# nrf5340_qkaa_Config3.net
KiCad netlist of a schematic drawn in EAGLE
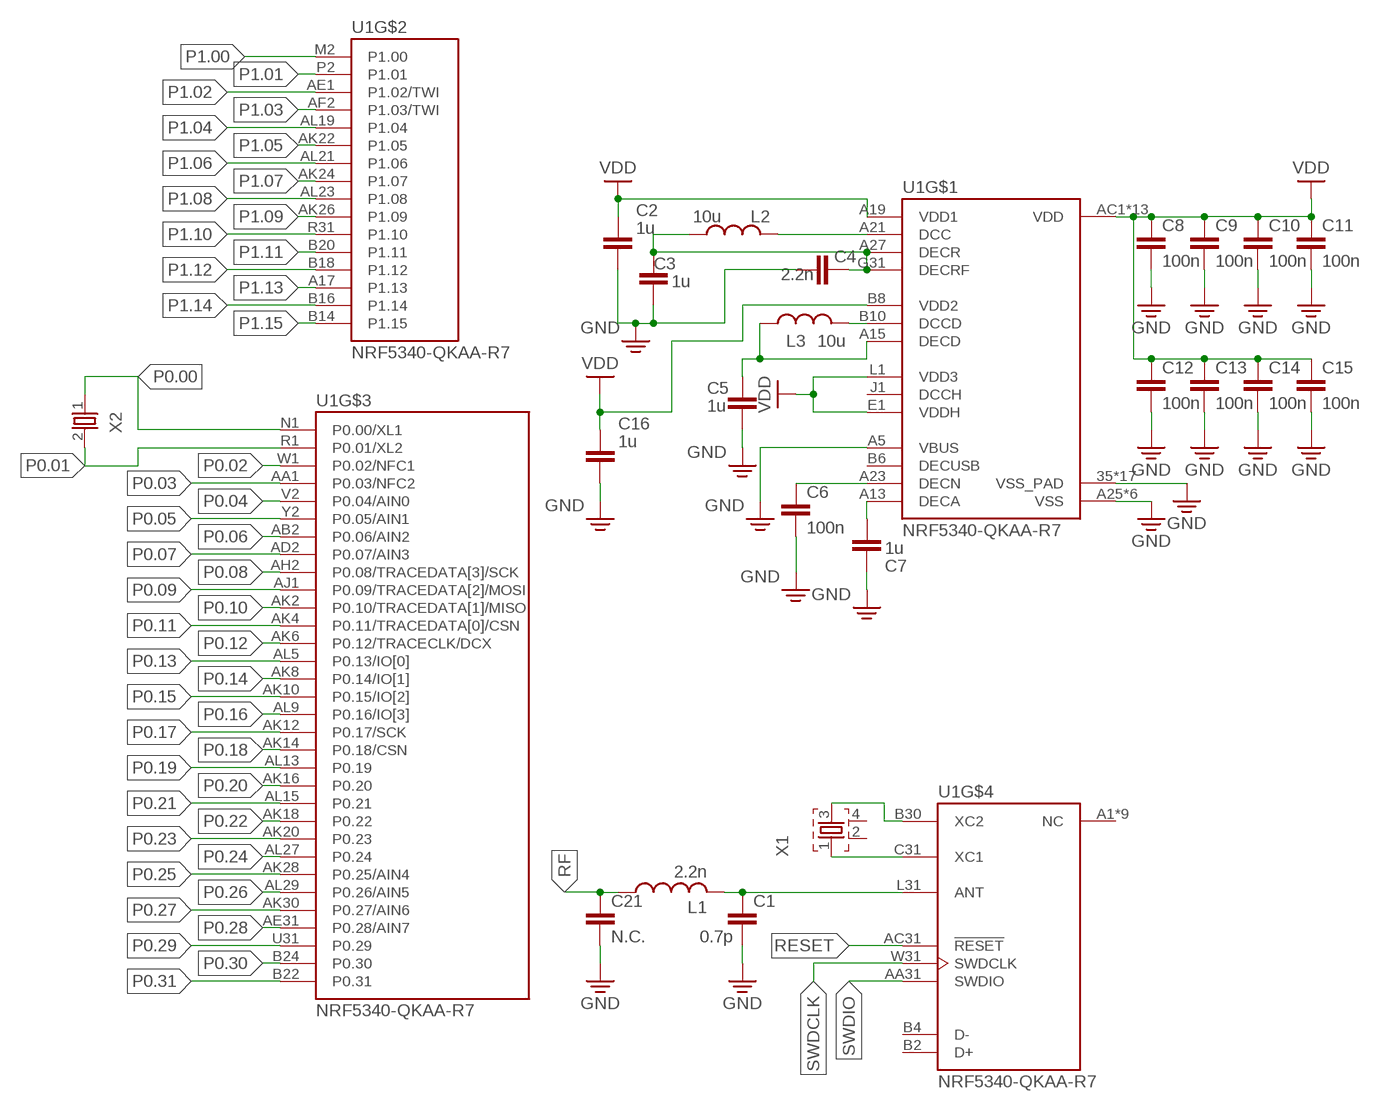
[diagram p0: schematic, sheet 1]

(export (version "E")
  (design (tool "Eeschema 10.0.6"))
  (components
    (comp (ref "C1")
      (value "0.7p")
      (footprint "eagle-import:RESC0201_N")
      (libsource (lib "eagle-import") (part "CAPACITOR_0201_N"))
    )
    (comp (ref "C2")
      (value "1u")
      (footprint "eagle-import:CAPC1005X60")
      (libsource (lib "eagle-import") (part "CCHIP-0402(1005-METRIC)_"))
    )
    (comp (ref "C3")
      (value "1u")
      (footprint "eagle-import:CAPC1005X60")
      (libsource (lib "eagle-import") (part "CCHIP-0402(1005-METRIC)_"))
    )
    (comp (ref "C4")
      (value "2.2n")
      (footprint "eagle-import:RESC0201_N")
      (libsource (lib "eagle-import") (part "CAPACITOR_0201_N"))
    )
    (comp (ref "C5")
      (value "1u")
      (footprint "eagle-import:CAPC1005X60")
      (libsource (lib "eagle-import") (part "CCHIP-0402(1005-METRIC)_"))
    )
    (comp (ref "C6")
      (value "100n")
      (footprint "eagle-import:RESC0201_N")
      (libsource (lib "eagle-import") (part "CAPACITOR_0201_N"))
    )
    (comp (ref "C7")
      (value "1u")
      (footprint "eagle-import:CAPC1005X60")
      (libsource (lib "eagle-import") (part "CCHIP-0402(1005-METRIC)_"))
    )
    (comp (ref "C8")
      (value "100n")
      (footprint "eagle-import:RESC0201_N")
      (libsource (lib "eagle-import") (part "CAPACITOR_0201_N"))
    )
    (comp (ref "C9")
      (value "100n")
      (footprint "eagle-import:RESC0201_N")
      (libsource (lib "eagle-import") (part "CAPACITOR_0201_N"))
    )
    (comp (ref "C10")
      (value "100n")
      (footprint "eagle-import:RESC0201_N")
      (libsource (lib "eagle-import") (part "CAPACITOR_0201_N"))
    )
    (comp (ref "C11")
      (value "100n")
      (footprint "eagle-import:RESC0201_N")
      (libsource (lib "eagle-import") (part "CAPACITOR_0201_N"))
    )
    (comp (ref "C12")
      (value "100n")
      (footprint "eagle-import:RESC0201_N")
      (libsource (lib "eagle-import") (part "CAPACITOR_0201_N"))
    )
    (comp (ref "C13")
      (value "100n")
      (footprint "eagle-import:RESC0201_N")
      (libsource (lib "eagle-import") (part "CAPACITOR_0201_N"))
    )
    (comp (ref "C14")
      (value "100n")
      (footprint "eagle-import:RESC0201_N")
      (libsource (lib "eagle-import") (part "CAPACITOR_0201_N"))
    )
    (comp (ref "C15")
      (value "100n")
      (footprint "eagle-import:RESC0201_N")
      (libsource (lib "eagle-import") (part "CAPACITOR_0201_N"))
    )
    (comp (ref "C16")
      (value "1u")
      (footprint "eagle-import:CAPC1005X60")
      (libsource (lib "eagle-import") (part "CCHIP-0402(1005-METRIC)_"))
    )
    (comp (ref "C21")
      (value "N.C.")
      (footprint "eagle-import:RESC0201_N")
      (libsource (lib "eagle-import") (part "CAPACITOR_0201_N"))
    )
    (comp (ref "L1")
      (value "2.2n")
      (footprint "eagle-import:RESC0201_N")
      (libsource (lib "eagle-import") (part "INDUCTOR_0201_N"))
    )
    (comp (ref "L2")
      (value "10u")
      (footprint "eagle-import:INDC1608X95N")
      (libsource (lib "eagle-import") (part "LCHIP-0603(1608-METRIC)_"))
    )
    (comp (ref "L3")
      (value "10u")
      (footprint "eagle-import:INDC1608X95N")
      (libsource (lib "eagle-import") (part "LCHIP-0603(1608-METRIC)_"))
    )
    (comp (ref "U1")
      (value "NRF5340-QKAA-R7")
      (footprint "eagle-import:XCVR_NRF5340-QKAA-R7")
      (fields (field (name "MANUFACTURER") "Nordic Semiconductor"))
      (libsource (lib "eagle-import") (part "NRF5340-QKAA-R7"))
    )
    (comp (ref "X1")
      (value "XTAL_32MHZ")
      (footprint "eagle-import:BT-XTAL_2016_N")
      (libsource (lib "eagle-import") (part "XTAL_32MHZ"))
    )
    (comp (ref "X2")
      (value "XTAL_32KHZ")
      (footprint "eagle-import:XTAL_3215_N")
      (libsource (lib "eagle-import") (part "XTAL_32KHZ"))
    )
  )
  (nets
    (net (code "1") (name "/DCCH") (class "Default")
      (node (ref "U1") (pin "J1") (pinfunction "DCCH_J1") (pintype "power_in"))
    )
    (net (code "2") (name "/DECUSB") (class "Default")
      (node (ref "U1") (pin "B6") (pinfunction "DECUSB_B6") (pintype "power_in"))
    )
    (net (code "3") (name "GND") (class "Default")
      (node (ref "C1") (pin "2") (pinfunction "2_2") (pintype "passive"))
      (node (ref "C10") (pin "2") (pinfunction "2_2") (pintype "passive"))
      (node (ref "C11") (pin "2") (pinfunction "2_2") (pintype "passive"))
      (node (ref "C12") (pin "2") (pinfunction "2_2") (pintype "passive"))
      (node (ref "C13") (pin "2") (pinfunction "2_2") (pintype "passive"))
      (node (ref "C14") (pin "2") (pinfunction "2_2") (pintype "passive"))
      (node (ref "C15") (pin "2") (pinfunction "2_2") (pintype "passive"))
      (node (ref "C16") (pin "2") (pinfunction "2_2") (pintype "passive"))
      (node (ref "C2") (pin "2") (pinfunction "2_2") (pintype "passive"))
      (node (ref "C21") (pin "2") (pinfunction "2_2") (pintype "passive"))
      (node (ref "C3") (pin "2") (pinfunction "2_2") (pintype "passive"))
      (node (ref "C4") (pin "2") (pinfunction "2_2") (pintype "passive"))
      (node (ref "C5") (pin "2") (pinfunction "2_2") (pintype "passive"))
      (node (ref "C6") (pin "2") (pinfunction "2_2") (pintype "passive"))
      (node (ref "C7") (pin "2") (pinfunction "2_2") (pintype "passive"))
      (node (ref "C8") (pin "2") (pinfunction "2_2") (pintype "passive"))
      (node (ref "C9") (pin "2") (pinfunction "2_2") (pintype "passive"))
      (node (ref "U1") (pin "104") (pinfunction "VSS_PAD_104") (pintype "power_in"))
      (node (ref "U1") (pin "35") (pinfunction "VSS_PAD_35") (pintype "power_in"))
      (node (ref "U1") (pin "36") (pinfunction "VSS_PAD_36") (pintype "power_in"))
      (node (ref "U1") (pin "37") (pinfunction "VSS_PAD_37") (pintype "power_in"))
      (node (ref "U1") (pin "38") (pinfunction "VSS_PAD_38") (pintype "power_in"))
      (node (ref "U1") (pin "39") (pinfunction "VSS_PAD_39") (pintype "power_in"))
      (node (ref "U1") (pin "40") (pinfunction "VSS_PAD_40") (pintype "power_in"))
      (node (ref "U1") (pin "41") (pinfunction "VSS_PAD_41") (pintype "power_in"))
      (node (ref "U1") (pin "43") (pinfunction "VSS_PAD_43") (pintype "power_in"))
      (node (ref "U1") (pin "44") (pinfunction "VSS_PAD_44") (pintype "power_in"))
      (node (ref "U1") (pin "45") (pinfunction "VSS_PAD_45") (pintype "power_in"))
      (node (ref "U1") (pin "46") (pinfunction "VSS_PAD_46") (pintype "power_in"))
      (node (ref "U1") (pin "47") (pinfunction "VSS_PAD_47") (pintype "power_in"))
      (node (ref "U1") (pin "48") (pinfunction "VSS_PAD_48") (pintype "power_in"))
      (node (ref "U1") (pin "49") (pinfunction "VSS_PAD_49") (pintype "power_in"))
      (node (ref "U1") (pin "50") (pinfunction "VSS_PAD_50") (pintype "power_in"))
      (node (ref "U1") (pin "51") (pinfunction "VSS_PAD_51") (pintype "power_in"))
      (node (ref "U1") (pin "A25") (pinfunction "VSS_A25") (pintype "power_in"))
      (node (ref "U1") (pin "A5") (pinfunction "VBUS_A5") (pintype "power_in"))
      (node (ref "U1") (pin "B12") (pinfunction "VSS_B12") (pintype "power_in"))
      (node (ref "U1") (pin "B26") (pinfunction "VSS_B26") (pintype "power_in"))
      (node (ref "U1") (pin "G1") (pinfunction "VSS_G1") (pintype "power_in"))
      (node (ref "U1") (pin "H2") (pinfunction "VSS_H2") (pintype "power_in"))
      (node (ref "U1") (pin "J31") (pinfunction "VSS_J31") (pintype "power_in"))
    )
    (net (code "4") (name "Net-(U1A-DCC)") (class "Default")
      (node (ref "L2") (pin "2") (pinfunction "2_2") (pintype "passive"))
      (node (ref "U1") (pin "A21") (pinfunction "DCC_A21") (pintype "power_in"))
    )
    (net (code "5") (name "Net-(U1A-DCCD)") (class "Default")
      (node (ref "L3") (pin "2") (pinfunction "2_2") (pintype "passive"))
      (node (ref "U1") (pin "B10") (pinfunction "DCCD_B10") (pintype "power_in"))
    )
    (net (code "6") (name "Net-(U1A-DECA)") (class "Default")
      (node (ref "C7") (pin "1") (pinfunction "1_1") (pintype "passive"))
      (node (ref "U1") (pin "A13") (pinfunction "DECA_A13") (pintype "power_in"))
    )
    (net (code "7") (name "Net-(U1A-DECD)") (class "Default")
      (node (ref "C5") (pin "1") (pinfunction "1_1") (pintype "passive"))
      (node (ref "L3") (pin "1") (pinfunction "1_1") (pintype "passive"))
      (node (ref "U1") (pin "A15") (pinfunction "DECD_A15") (pintype "power_in"))
    )
    (net (code "8") (name "Net-(U1A-DECN)") (class "Default")
      (node (ref "C6") (pin "1") (pinfunction "1_1") (pintype "passive"))
      (node (ref "U1") (pin "A23") (pinfunction "DECN_A23") (pintype "power_in"))
    )
    (net (code "9") (name "Net-(U1A-DECR)") (class "Default")
      (node (ref "C3") (pin "1") (pinfunction "1_1") (pintype "passive"))
      (node (ref "C4") (pin "1") (pinfunction "1_1") (pintype "passive"))
      (node (ref "L2") (pin "1") (pinfunction "1_1") (pintype "passive"))
      (node (ref "U1") (pin "A27") (pinfunction "DECR_A27") (pintype "power_in"))
      (node (ref "U1") (pin "G31") (pinfunction "DECRF_G31") (pintype "power_in"))
    )
    (net (code "10") (name "Net-(U1D-ANT)") (class "Default")
      (node (ref "C1") (pin "1") (pinfunction "1_1") (pintype "passive"))
      (node (ref "L1") (pin "2") (pinfunction "2_2") (pintype "passive"))
      (node (ref "U1") (pin "L31") (pinfunction "ANT_L31") (pintype "bidirectional"))
    )
    (net (code "11") (name "Net-(U1D-XC1)") (class "Default")
      (node (ref "U1") (pin "C31") (pinfunction "XC1_C31") (pintype "input"))
      (node (ref "X1") (pin "1") (pinfunction "1_1") (pintype "passive"))
    )
    (net (code "12") (name "Net-(U1D-XC2)") (class "Default")
      (node (ref "U1") (pin "B30") (pinfunction "XC2_B30") (pintype "output"))
      (node (ref "X1") (pin "3") (pinfunction "3_3") (pintype "passive"))
    )
    (net (code "13") (name "P0.00") (class "Default")
      (node (ref "U1") (pin "N1") (pinfunction "P0.00/XL1_N1") (pintype "bidirectional"))
      (node (ref "X2") (pin "1") (pinfunction "1_1") (pintype "passive"))
    )
    (net (code "14") (name "P0.01") (class "Default")
      (node (ref "U1") (pin "R1") (pinfunction "P0.01/XL2_R1") (pintype "bidirectional"))
      (node (ref "X2") (pin "2") (pinfunction "2_2") (pintype "passive"))
    )
    (net (code "15") (name "P0.02") (class "Default")
      (node (ref "U1") (pin "W1") (pinfunction "P0.02/NFC1_W1") (pintype "bidirectional"))
    )
    (net (code "16") (name "P0.03") (class "Default")
      (node (ref "U1") (pin "AA1") (pinfunction "P0.03/NFC2_AA1") (pintype "bidirectional"))
    )
    (net (code "17") (name "P0.04") (class "Default")
      (node (ref "U1") (pin "V2") (pinfunction "P0.04/AIN0_V2") (pintype "bidirectional"))
    )
    (net (code "18") (name "P0.05") (class "Default")
      (node (ref "U1") (pin "Y2") (pinfunction "P0.05/AIN1_Y2") (pintype "bidirectional"))
    )
    (net (code "19") (name "P0.06") (class "Default")
      (node (ref "U1") (pin "AB2") (pinfunction "P0.06/AIN2_AB2") (pintype "bidirectional"))
    )
    (net (code "20") (name "P0.07") (class "Default")
      (node (ref "U1") (pin "AD2") (pinfunction "P0.07/AIN3_AD2") (pintype "bidirectional"))
    )
    (net (code "21") (name "P0.08") (class "Default")
      (node (ref "U1") (pin "AH2") (pinfunction "P0.08/TRACEDATA[3]/SCK_AH2") (pintype "bidirectional"))
    )
    (net (code "22") (name "P0.09") (class "Default")
      (node (ref "U1") (pin "AJ1") (pinfunction "P0.09/TRACEDATA[2]/MOSI_AJ1") (pintype "bidirectional"))
    )
    (net (code "23") (name "P0.10") (class "Default")
      (node (ref "U1") (pin "AK2") (pinfunction "P0.10/TRACEDATA[1]/MISO_AK2") (pintype "bidirectional"))
    )
    (net (code "24") (name "P0.11") (class "Default")
      (node (ref "U1") (pin "AK4") (pinfunction "P0.11/TRACEDATA[0]/CSN_AK4") (pintype "bidirectional"))
    )
    (net (code "25") (name "P0.12") (class "Default")
      (node (ref "U1") (pin "AK6") (pinfunction "P0.12/TRACECLK/DCX_AK6") (pintype "bidirectional"))
    )
    (net (code "26") (name "P0.13") (class "Default")
      (node (ref "U1") (pin "AL5") (pinfunction "P0.13/IO[0]_AL5") (pintype "bidirectional"))
    )
    (net (code "27") (name "P0.14") (class "Default")
      (node (ref "U1") (pin "AK8") (pinfunction "P0.14/IO[1]_AK8") (pintype "bidirectional"))
    )
    (net (code "28") (name "P0.15") (class "Default")
      (node (ref "U1") (pin "AK10") (pinfunction "P0.15/IO[2]_AK10") (pintype "bidirectional"))
    )
    (net (code "29") (name "P0.16") (class "Default")
      (node (ref "U1") (pin "AL9") (pinfunction "P0.16/IO[3]_AL9") (pintype "bidirectional"))
    )
    (net (code "30") (name "P0.17") (class "Default")
      (node (ref "U1") (pin "AK12") (pinfunction "P0.17/SCK_AK12") (pintype "bidirectional"))
    )
    (net (code "31") (name "P0.18") (class "Default")
      (node (ref "U1") (pin "AK14") (pinfunction "P0.18/CSN_AK14") (pintype "bidirectional"))
    )
    (net (code "32") (name "P0.19") (class "Default")
      (node (ref "U1") (pin "AL13") (pinfunction "P0.19_AL13") (pintype "bidirectional"))
    )
    (net (code "33") (name "P0.20") (class "Default")
      (node (ref "U1") (pin "AK16") (pinfunction "P0.20_AK16") (pintype "bidirectional"))
    )
    (net (code "34") (name "P0.21") (class "Default")
      (node (ref "U1") (pin "AL15") (pinfunction "P0.21_AL15") (pintype "bidirectional"))
    )
    (net (code "35") (name "P0.22") (class "Default")
      (node (ref "U1") (pin "AK18") (pinfunction "P0.22_AK18") (pintype "bidirectional"))
    )
    (net (code "36") (name "P0.23") (class "Default")
      (node (ref "U1") (pin "AK20") (pinfunction "P0.23_AK20") (pintype "bidirectional"))
    )
    (net (code "37") (name "P0.24") (class "Default")
      (node (ref "U1") (pin "AL27") (pinfunction "P0.24_AL27") (pintype "bidirectional"))
    )
    (net (code "38") (name "P0.25") (class "Default")
      (node (ref "U1") (pin "AK28") (pinfunction "P0.25/AIN4_AK28") (pintype "bidirectional"))
    )
    (net (code "39") (name "P0.26") (class "Default")
      (node (ref "U1") (pin "AL29") (pinfunction "P0.26/AIN5_AL29") (pintype "bidirectional"))
    )
    (net (code "40") (name "P0.27") (class "Default")
      (node (ref "U1") (pin "AK30") (pinfunction "P0.27/AIN6_AK30") (pintype "bidirectional"))
    )
    (net (code "41") (name "P0.28") (class "Default")
      (node (ref "U1") (pin "AE31") (pinfunction "P0.28/AIN7_AE31") (pintype "bidirectional"))
    )
    (net (code "42") (name "P0.29") (class "Default")
      (node (ref "U1") (pin "U31") (pinfunction "P0.29_U31") (pintype "bidirectional"))
    )
    (net (code "43") (name "P0.30") (class "Default")
      (node (ref "U1") (pin "B24") (pinfunction "P0.30_B24") (pintype "bidirectional"))
    )
    (net (code "44") (name "P0.31") (class "Default")
      (node (ref "U1") (pin "B22") (pinfunction "P0.31_B22") (pintype "bidirectional"))
    )
    (net (code "45") (name "P1.00") (class "Default")
      (node (ref "U1") (pin "M2") (pinfunction "P1.00_M2") (pintype "bidirectional"))
    )
    (net (code "46") (name "P1.01") (class "Default")
      (node (ref "U1") (pin "P2") (pinfunction "P1.01_P2") (pintype "bidirectional"))
    )
    (net (code "47") (name "P1.02") (class "Default")
      (node (ref "U1") (pin "AE1") (pinfunction "P1.02/TWI_AE1") (pintype "bidirectional"))
    )
    (net (code "48") (name "P1.03") (class "Default")
      (node (ref "U1") (pin "AF2") (pinfunction "P1.03/TWI_AF2") (pintype "bidirectional"))
    )
    (net (code "49") (name "P1.04") (class "Default")
      (node (ref "U1") (pin "AL19") (pinfunction "P1.04_AL19") (pintype "bidirectional"))
    )
    (net (code "50") (name "P1.05") (class "Default")
      (node (ref "U1") (pin "AK22") (pinfunction "P1.05_AK22") (pintype "bidirectional"))
    )
    (net (code "51") (name "P1.06") (class "Default")
      (node (ref "U1") (pin "AL21") (pinfunction "P1.06_AL21") (pintype "bidirectional"))
    )
    (net (code "52") (name "P1.07") (class "Default")
      (node (ref "U1") (pin "AK24") (pinfunction "P1.07_AK24") (pintype "bidirectional"))
    )
    (net (code "53") (name "P1.08") (class "Default")
      (node (ref "U1") (pin "AL23") (pinfunction "P1.08_AL23") (pintype "bidirectional"))
    )
    (net (code "54") (name "P1.09") (class "Default")
      (node (ref "U1") (pin "AK26") (pinfunction "P1.09_AK26") (pintype "bidirectional"))
    )
    (net (code "55") (name "P1.10") (class "Default")
      (node (ref "U1") (pin "R31") (pinfunction "P1.10_R31") (pintype "bidirectional"))
    )
    (net (code "56") (name "P1.11") (class "Default")
      (node (ref "U1") (pin "B20") (pinfunction "P1.11_B20") (pintype "bidirectional"))
    )
    (net (code "57") (name "P1.12") (class "Default")
      (node (ref "U1") (pin "B18") (pinfunction "P1.12_B18") (pintype "bidirectional"))
    )
    (net (code "58") (name "P1.13") (class "Default")
      (node (ref "U1") (pin "A17") (pinfunction "P1.13_A17") (pintype "bidirectional"))
    )
    (net (code "59") (name "P1.14") (class "Default")
      (node (ref "U1") (pin "B16") (pinfunction "P1.14_B16") (pintype "bidirectional"))
    )
    (net (code "60") (name "P1.15") (class "Default")
      (node (ref "U1") (pin "B14") (pinfunction "P1.15_B14") (pintype "bidirectional"))
    )
    (net (code "61") (name "RESET") (class "Default")
      (node (ref "U1") (pin "AC31") (pinfunction "~{RESET}_AC31") (pintype "input"))
    )
    (net (code "62") (name "RF") (class "Default")
      (node (ref "C21") (pin "1") (pinfunction "1_1") (pintype "passive"))
      (node (ref "L1") (pin "1") (pinfunction "1_1") (pintype "passive"))
    )
    (net (code "63") (name "SWDCLK") (class "Default")
      (node (ref "U1") (pin "W31") (pinfunction "SWDCLK_W31") (pintype "input"))
    )
    (net (code "64") (name "SWDIO") (class "Default")
      (node (ref "U1") (pin "AA31") (pinfunction "SWDIO_AA31") (pintype "bidirectional"))
    )
    (net (code "65") (name "VDD") (class "Default")
      (node (ref "C10") (pin "1") (pinfunction "1_1") (pintype "passive"))
      (node (ref "C11") (pin "1") (pinfunction "1_1") (pintype "passive"))
      (node (ref "C12") (pin "1") (pinfunction "1_1") (pintype "passive"))
      (node (ref "C13") (pin "1") (pinfunction "1_1") (pintype "passive"))
      (node (ref "C14") (pin "1") (pinfunction "1_1") (pintype "passive"))
      (node (ref "C15") (pin "1") (pinfunction "1_1") (pintype "passive"))
      (node (ref "C16") (pin "1") (pinfunction "1_1") (pintype "passive"))
      (node (ref "C2") (pin "1") (pinfunction "1_1") (pintype "passive"))
      (node (ref "C8") (pin "1") (pinfunction "1_1") (pintype "passive"))
      (node (ref "C9") (pin "1") (pinfunction "1_1") (pintype "passive"))
      (node (ref "U1") (pin "A19") (pinfunction "VDD1_A19") (pintype "power_in"))
      (node (ref "U1") (pin "AC1") (pinfunction "VDD_AC1") (pintype "power_in"))
      (node (ref "U1") (pin "AG1") (pinfunction "VDD_AG1") (pintype "power_in"))
      (node (ref "U1") (pin "AJ31") (pinfunction "VDD_AJ31") (pintype "power_in"))
      (node (ref "U1") (pin "AL11") (pinfunction "VDD_AL11") (pintype "power_in"))
      (node (ref "U1") (pin "AL17") (pinfunction "VDD_AL17") (pintype "power_in"))
      (node (ref "U1") (pin "AL25") (pinfunction "VDD_AL25") (pintype "power_in"))
      (node (ref "U1") (pin "AL3") (pinfunction "VDD_AL3") (pintype "power_in"))
      (node (ref "U1") (pin "AL7") (pinfunction "VDD_AL7") (pintype "power_in"))
      (node (ref "U1") (pin "B28") (pinfunction "VDD_B28") (pintype "power_in"))
      (node (ref "U1") (pin "B8") (pinfunction "VDD2_B8") (pintype "power_in"))
      (node (ref "U1") (pin "C1") (pinfunction "VDD_C1") (pintype "power_in"))
      (node (ref "U1") (pin "E1") (pinfunction "VDDH_E1") (pintype "power_in"))
      (node (ref "U1") (pin "E31") (pinfunction "VDD_E31") (pintype "power_in"))
      (node (ref "U1") (pin "L1") (pinfunction "VDD3_L1") (pintype "power_in"))
      (node (ref "U1") (pin "N31") (pinfunction "VDD_N31") (pintype "power_in"))
      (node (ref "U1") (pin "U1") (pinfunction "VDD_U1") (pintype "power_in"))
    )
    (net (code "66") (name "unconnected-(U1D-D+-PadB2)") (class "Default")
      (node (ref "U1") (pin "B2") (pinfunction "D+_B2") (pintype "bidirectional"))
    )
    (net (code "67") (name "unconnected-(U1D-D--PadB4)") (class "Default")
      (node (ref "U1") (pin "B4") (pinfunction "D-_B4") (pintype "bidirectional"))
    )
    (net (code "68") (name "unconnected-(U1D-NC-PadA1)") (class "Default")
      (node (ref "U1") (pin "A1") (pinfunction "NC_A1") (pintype "no_connect"))
    )
    (net (code "69") (name "unconnected-(U1D-NC-PadA31)") (class "Default")
      (node (ref "U1") (pin "A31") (pinfunction "NC_A31") (pintype "no_connect"))
    )
    (net (code "70") (name "unconnected-(U1D-NC-PadAG31)") (class "Default")
      (node (ref "U1") (pin "AG31") (pinfunction "NC_AG31") (pintype "no_connect"))
    )
    (net (code "71") (name "unconnected-(U1D-NC-PadAL1)") (class "Default")
      (node (ref "U1") (pin "AL1") (pinfunction "NC_AL1") (pintype "no_connect"))
    )
    (net (code "72") (name "unconnected-(U1D-NC-PadAL31)") (class "Default")
      (node (ref "U1") (pin "AL31") (pinfunction "NC_AL31") (pintype "no_connect"))
    )
    (net (code "73") (name "unconnected-(U1D-NC-PadD2)") (class "Default")
      (node (ref "U1") (pin "D2") (pinfunction "NC_D2") (pintype "no_connect"))
    )
    (net (code "74") (name "unconnected-(U1D-NC-PadF2)") (class "Default")
      (node (ref "U1") (pin "F2") (pinfunction "NC_F2") (pintype "no_connect"))
    )
    (net (code "75") (name "unconnected-(U1D-NC-PadK2)") (class "Default")
      (node (ref "U1") (pin "K2") (pinfunction "NC_K2") (pintype "no_connect"))
    )
    (net (code "76") (name "unconnected-(U1D-NC-PadT2)") (class "Default")
      (node (ref "U1") (pin "T2") (pinfunction "NC_T2") (pintype "no_connect"))
    )
    (net (code "77") (name "unconnected-(X1-Pad2)") (class "Default")
      (node (ref "X1") (pin "2") (pinfunction "2_2") (pintype "passive"))
    )
    (net (code "78") (name "unconnected-(X1-Pad4)") (class "Default")
      (node (ref "X1") (pin "4") (pinfunction "4_4") (pintype "passive"))
    )
  )
)
